# Supply_0.net
KiCad netlist of a schematic drawn in Altium Designer
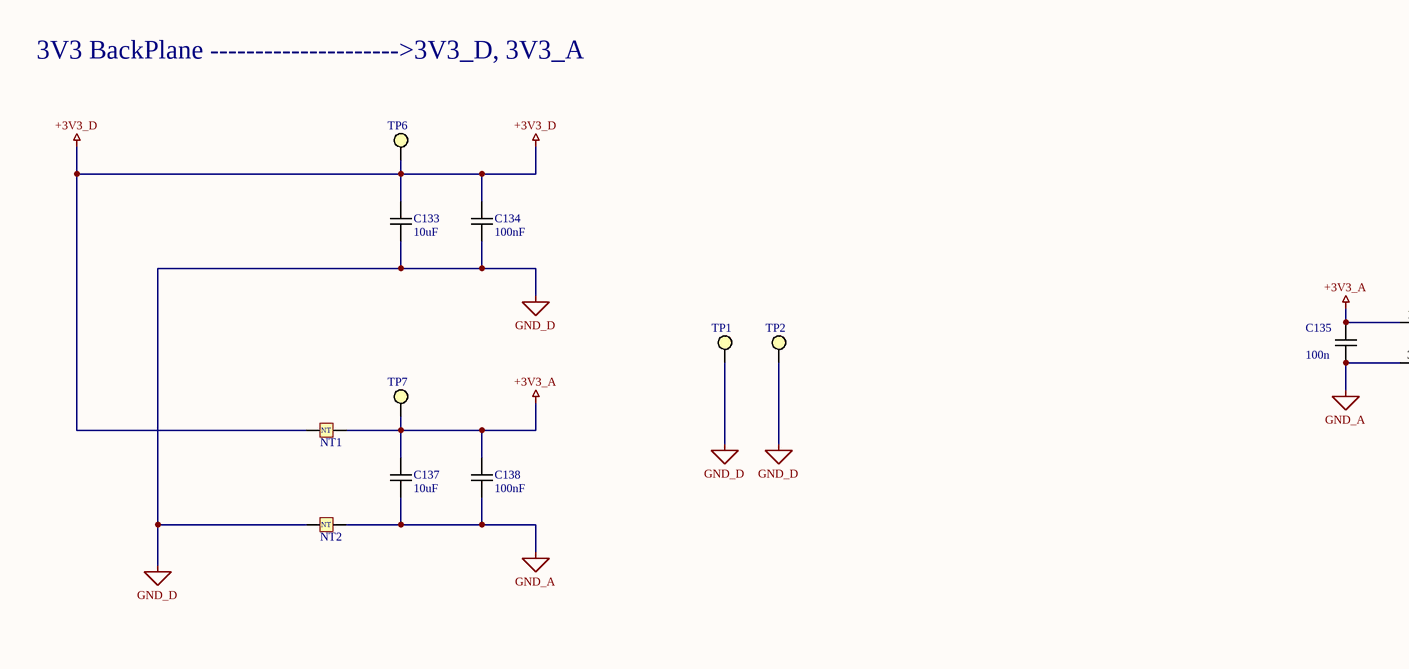
[diagram p0: Supply_0.SchDoc, left]
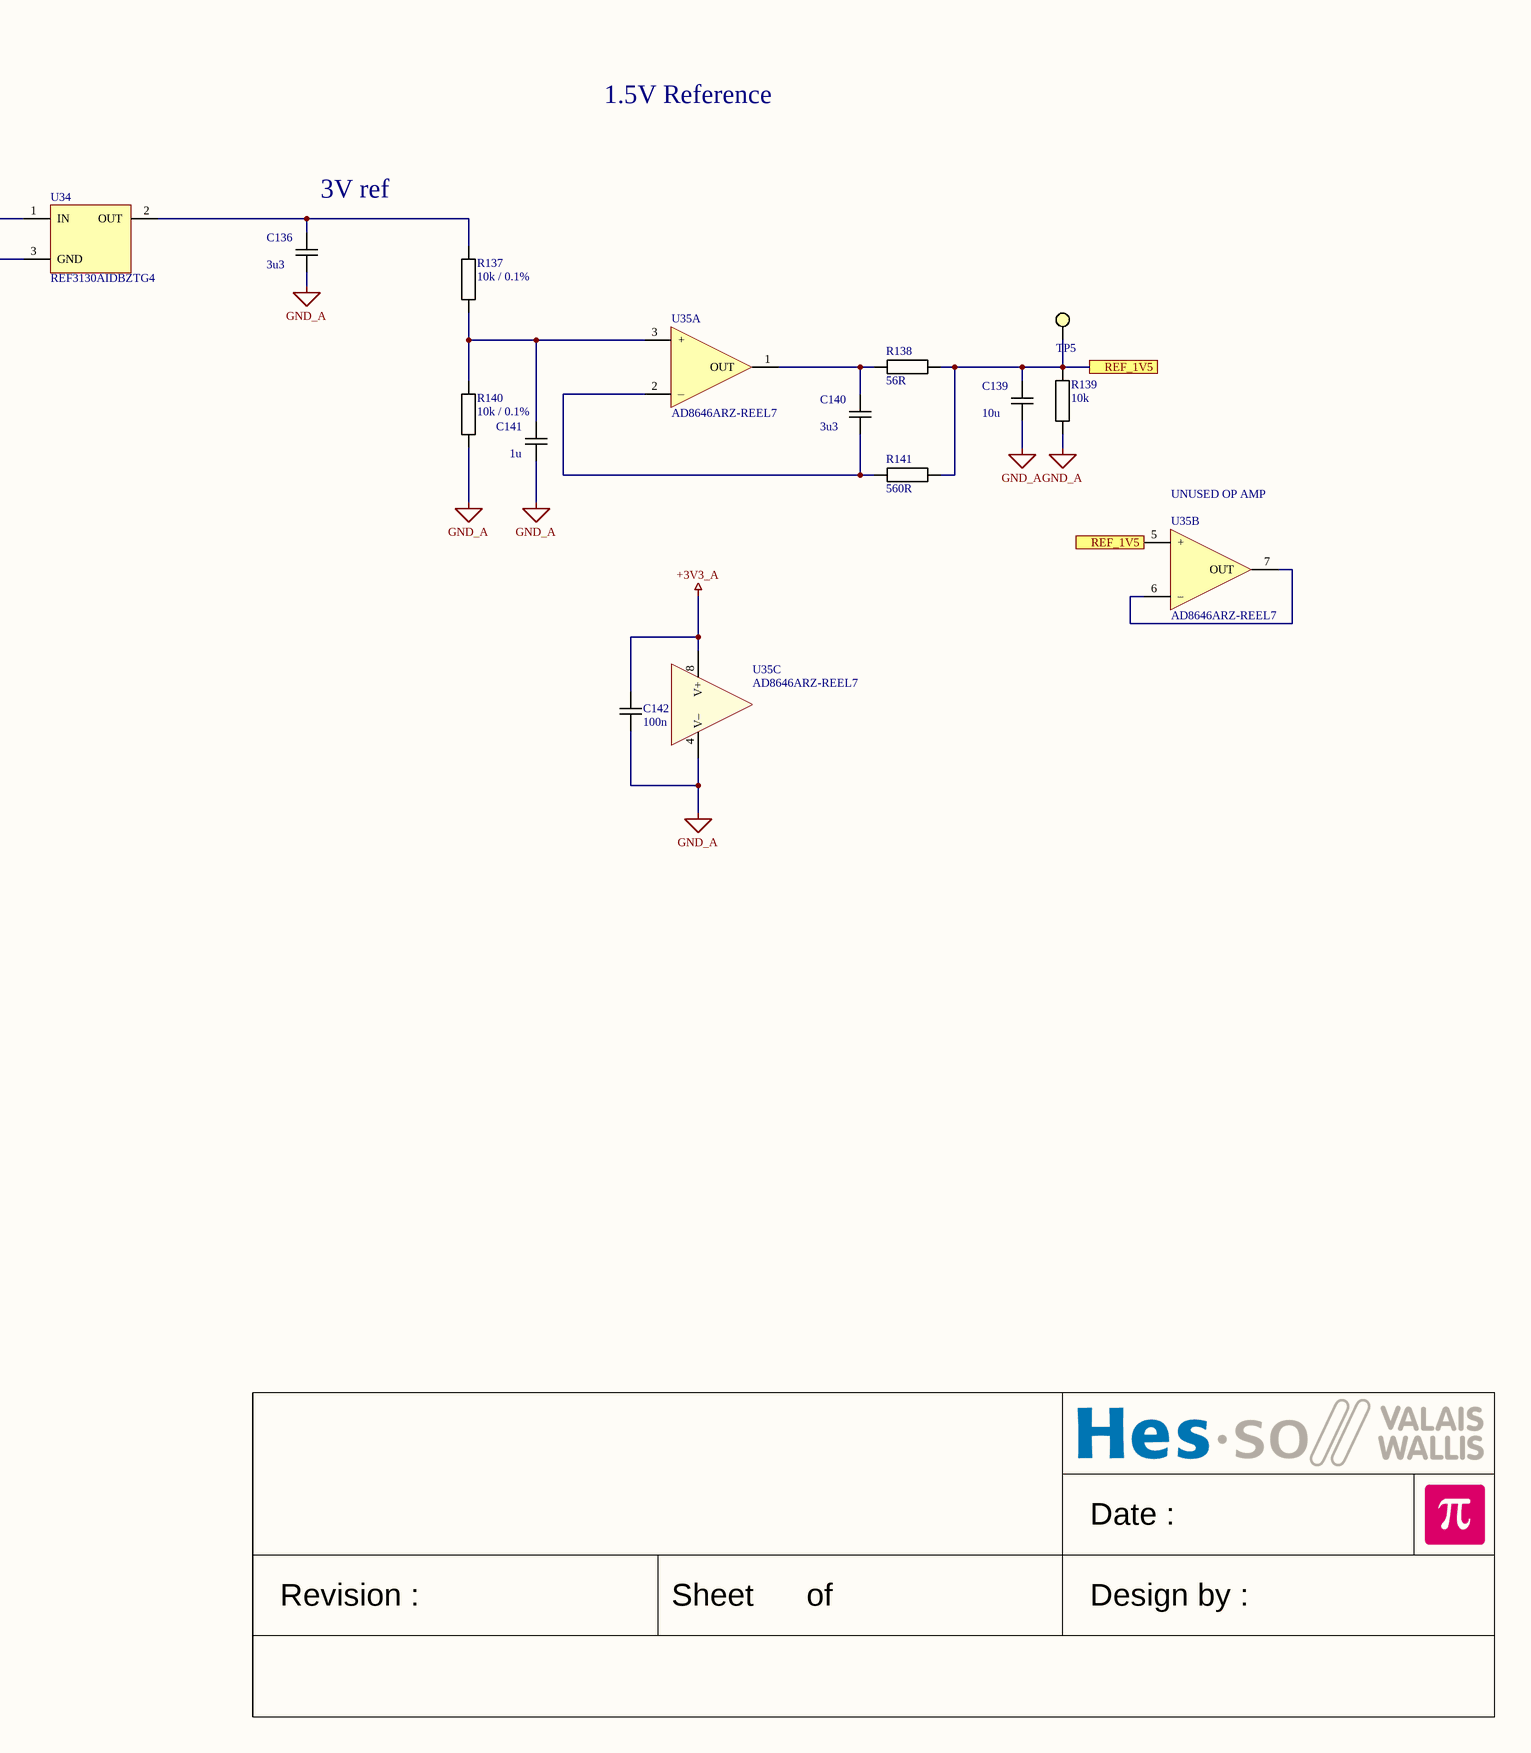
[diagram p1: Supply_0.SchDoc, right]

(export (version "E")
  (design (tool "Eeschema 10.0.6"))
  (components
    (comp (ref "C133")
      (value "10uF")
      (footprint "CAPACITOR 2012 REFLOW")
      (description "Capacitor X7R 10% 10V 2012(0805)")
      (libsource (lib "Capacitor") (part "Capacitor"))
    )
    (comp (ref "C134")
      (value "100nF")
      (footprint "CAPACITOR 2012 REFLOW")
      (description "Capacitor X7R 10% 50V 2012(0805)")
      (libsource (lib "Capacitor") (part "Capacitor"))
    )
    (comp (ref "C135")
      (value "100n")
      (footprint "CAPACITOR 1608 REFLOW")
      (description "Capacitor X7R 10% 50V 1608(0603)")
      (libsource (lib "Capacitor") (part "Capacitor"))
    )
    (comp (ref "C136")
      (value "3u3")
      (footprint "CAPACITOR 2012 REFLOW")
      (description "Capacitor X7R 10% 10V 2012(0805)")
      (libsource (lib "Capacitor") (part "Capacitor"))
    )
    (comp (ref "C137")
      (value "10uF")
      (footprint "CAPACITOR 2012 REFLOW")
      (description "Capacitor X7R 10% 10V 2012(0805)")
      (libsource (lib "Capacitor") (part "Capacitor"))
    )
    (comp (ref "C138")
      (value "100nF")
      (footprint "CAPACITOR 2012 REFLOW")
      (description "Capacitor X7R 10% 50V 2012(0805)")
      (libsource (lib "Capacitor") (part "Capacitor"))
    )
    (comp (ref "C139")
      (value "10u")
      (footprint "CAPACITOR 2012 REFLOW")
      (description "Capacitor X7R 10% 10V 2012(0805)")
      (libsource (lib "Capacitor") (part "Capacitor"))
    )
    (comp (ref "C140")
      (value "3u3")
      (footprint "CAPACITOR 2012 REFLOW")
      (description "Capacitor X7R 10% 10V 2012(0805)")
      (libsource (lib "Capacitor") (part "Capacitor"))
    )
    (comp (ref "C141")
      (value "1u")
      (footprint "CAPACITOR 2012 REFLOW")
      (description "Capacitor X7R 10% 10V 2012(0805)")
      (libsource (lib "Capacitor") (part "Capacitor"))
    )
    (comp (ref "C142")
      (value "100n")
      (footprint "CAPACITOR 1608 REFLOW")
      (description "Capacitor X7R 10% 50V 1608(0603)")
      (libsource (lib "Capacitor") (part "Capacitor"))
    )
    (comp (ref "NT1")
      (value "Net Tie")
      (footprint "NET TIE 1005")
      (description "Connection for 2 different NETNAME")
      (libsource (lib "Jumper") (part "Net Tie"))
    )
    (comp (ref "NT2")
      (value "Net Tie")
      (footprint "NET TIE 1005")
      (description "Connection for 2 different NETNAME")
      (libsource (lib "Jumper") (part "Net Tie"))
    )
    (comp (ref "R137")
      (value "10k / 0.1%")
      (footprint "RESISTOR 1608 REFLOW")
      (description "Resistor 1% 50V 100mW 1608(0603)")
      (libsource (lib "Resistor") (part "Resistor"))
    )
    (comp (ref "R138")
      (value "56R")
      (footprint "RESISTOR 1608 REFLOW")
      (description "Resistor 1% 50V 100mW 1608(0603)")
      (libsource (lib "Resistor") (part "Resistor"))
    )
    (comp (ref "R139")
      (value "10k")
      (footprint "RESISTOR 1608 REFLOW")
      (description "Resistor 1% 50V 100mW 1608(0603)")
      (libsource (lib "Resistor") (part "Resistor"))
    )
    (comp (ref "R140")
      (value "10k / 0.1%")
      (footprint "RESISTOR 1608 REFLOW")
      (description "Resistor 1% 50V 100mW 1608(0603)")
      (libsource (lib "Resistor") (part "Resistor"))
    )
    (comp (ref "R141")
      (value "560R")
      (footprint "RESISTOR 1608 REFLOW")
      (description "Resistor 1% 50V 100mW 1608(0603)")
      (libsource (lib "Resistor") (part "Resistor"))
    )
    (comp (ref "TP1")
      (value "*")
      (footprint "Test Point Keystone Miniature BLACK")
      (description "Test Point")
      (libsource (lib "Testpoint") (part "Test Point"))
    )
    (comp (ref "TP2")
      (value "*")
      (footprint "Test Point Keystone Miniature BLACK")
      (description "Test Point")
      (libsource (lib "Testpoint") (part "Test Point"))
    )
    (comp (ref "TP5")
      (value "*")
      (footprint "Test Point Keystone Miniature RED")
      (description "Test Point")
      (libsource (lib "Testpoint") (part "Test Point"))
    )
    (comp (ref "TP6")
      (value "*")
      (footprint "Test Point Keystone Miniature BLACK")
      (description "Test Point")
      (libsource (lib "Testpoint") (part "Test Point"))
    )
    (comp (ref "TP7")
      (value "*")
      (footprint "Test Point Keystone Miniature BLACK")
      (description "Test Point")
      (libsource (lib "Testpoint") (part "Test Point"))
    )
    (comp (ref "U34")
      (value "REF3130AIDBZTG4")
      (footprint "SOT23 P0.95 C1.6x3.0 H1.3")
      (description "Generic Positive Voltage Reference")
      (libsource (lib "Regulator") (part "REFERENCE SOT23 IN,OUT,GND"))
    )
    (comp (ref "U35")
      (value "AD8646ARZ-REEL7")
      (footprint "SO8 P1.27 C4.0X5.0 H1.75")
      (description "Generic dual OPA 8 pins")
      (fields (field (name "MANUFACTURER") "Analog Devices"))
      (libsource (lib "Amplifier") (part "OPA DUAL"))
    )
  )
  (nets
    (net (code "1") (name "+3V3_A") (class "Default")
      (node (ref "C135") (pin "2") (pinfunction "2_2") (pintype "passive"))
      (node (ref "C137") (pin "1") (pinfunction "1_1") (pintype "passive"))
      (node (ref "C138") (pin "1") (pinfunction "1_1") (pintype "passive"))
      (node (ref "C142") (pin "2") (pinfunction "2_2") (pintype "passive"))
      (node (ref "NT1") (pin "2") (pinfunction "2_2") (pintype "passive"))
      (node (ref "TP7") (pin "1") (pinfunction "1_1") (pintype "passive"))
      (node (ref "U34") (pin "1") (pinfunction "IN_1") (pintype "passive"))
      (node (ref "U35") (pin "8") (pinfunction "V+_8") (pintype "passive"))
    )
    (net (code "2") (name "+3V3_D") (class "Default")
      (node (ref "C133") (pin "1") (pinfunction "1_1") (pintype "passive"))
      (node (ref "C134") (pin "1") (pinfunction "1_1") (pintype "passive"))
      (node (ref "NT1") (pin "1") (pinfunction "1_1") (pintype "passive"))
      (node (ref "TP6") (pin "1") (pinfunction "1_1") (pintype "passive"))
    )
    (net (code "3") (name "/REF_1V5") (class "Default")
      (node (ref "C139") (pin "2") (pinfunction "2_2") (pintype "passive"))
      (node (ref "R138") (pin "1") (pinfunction "1_1") (pintype "passive"))
      (node (ref "R139") (pin "1") (pinfunction "1_1") (pintype "passive"))
      (node (ref "R141") (pin "1") (pinfunction "1_1") (pintype "passive"))
      (node (ref "TP5") (pin "1") (pinfunction "1_1") (pintype "passive"))
      (node (ref "U35") (pin "5") (pinfunction "+_5") (pintype "passive"))
    )
    (net (code "4") (name "GND_A") (class "Default")
      (node (ref "C135") (pin "1") (pinfunction "1_1") (pintype "passive"))
      (node (ref "C136") (pin "1") (pinfunction "1_1") (pintype "passive"))
      (node (ref "C137") (pin "2") (pinfunction "2_2") (pintype "passive"))
      (node (ref "C138") (pin "2") (pinfunction "2_2") (pintype "passive"))
      (node (ref "C139") (pin "1") (pinfunction "1_1") (pintype "passive"))
      (node (ref "C141") (pin "1") (pinfunction "1_1") (pintype "passive"))
      (node (ref "C142") (pin "1") (pinfunction "1_1") (pintype "passive"))
      (node (ref "NT2") (pin "2") (pinfunction "2_2") (pintype "passive"))
      (node (ref "R139") (pin "2") (pinfunction "2_2") (pintype "passive"))
      (node (ref "R140") (pin "2") (pinfunction "2_2") (pintype "passive"))
      (node (ref "U34") (pin "3") (pinfunction "GND_3") (pintype "passive"))
      (node (ref "U35") (pin "4") (pinfunction "V–_4") (pintype "passive"))
    )
    (net (code "5") (name "GND_D") (class "Default")
      (node (ref "C133") (pin "2") (pinfunction "2_2") (pintype "passive"))
      (node (ref "C134") (pin "2") (pinfunction "2_2") (pintype "passive"))
      (node (ref "NT2") (pin "1") (pinfunction "1_1") (pintype "passive"))
      (node (ref "TP1") (pin "1") (pinfunction "1_1") (pintype "passive"))
      (node (ref "TP2") (pin "1") (pinfunction "1_1") (pintype "passive"))
    )
    (net (code "6") (name "Net-(U34-OUT)") (class "Default")
      (node (ref "C136") (pin "2") (pinfunction "2_2") (pintype "passive"))
      (node (ref "R137") (pin "2") (pinfunction "2_2") (pintype "passive"))
      (node (ref "U34") (pin "2") (pinfunction "OUT_2") (pintype "passive"))
    )
    (net (code "7") (name "Net-(U35A-+)") (class "Default")
      (node (ref "C141") (pin "2") (pinfunction "2_2") (pintype "passive"))
      (node (ref "R137") (pin "1") (pinfunction "1_1") (pintype "passive"))
      (node (ref "R140") (pin "1") (pinfunction "1_1") (pintype "passive"))
      (node (ref "U35") (pin "3") (pinfunction "+_3") (pintype "passive"))
    )
    (net (code "8") (name "Net-(U35A-OUT)") (class "Default")
      (node (ref "C140") (pin "2") (pinfunction "2_2") (pintype "passive"))
      (node (ref "R138") (pin "2") (pinfunction "2_2") (pintype "passive"))
      (node (ref "U35") (pin "1") (pinfunction "OUT_1") (pintype "passive"))
    )
    (net (code "9") (name "Net-(U35A-–)") (class "Default")
      (node (ref "C140") (pin "1") (pinfunction "1_1") (pintype "passive"))
      (node (ref "R141") (pin "2") (pinfunction "2_2") (pintype "passive"))
      (node (ref "U35") (pin "2") (pinfunction "–_2") (pintype "passive"))
    )
    (net (code "10") (name "Net-(U35B-OUT)") (class "Default")
      (node (ref "U35") (pin "6") (pinfunction "–_6") (pintype "passive"))
      (node (ref "U35") (pin "7") (pinfunction "OUT_7") (pintype "passive"))
    )
  )
)
